# eth.net
KiCad netlist of a schematic drawn in Altium Designer
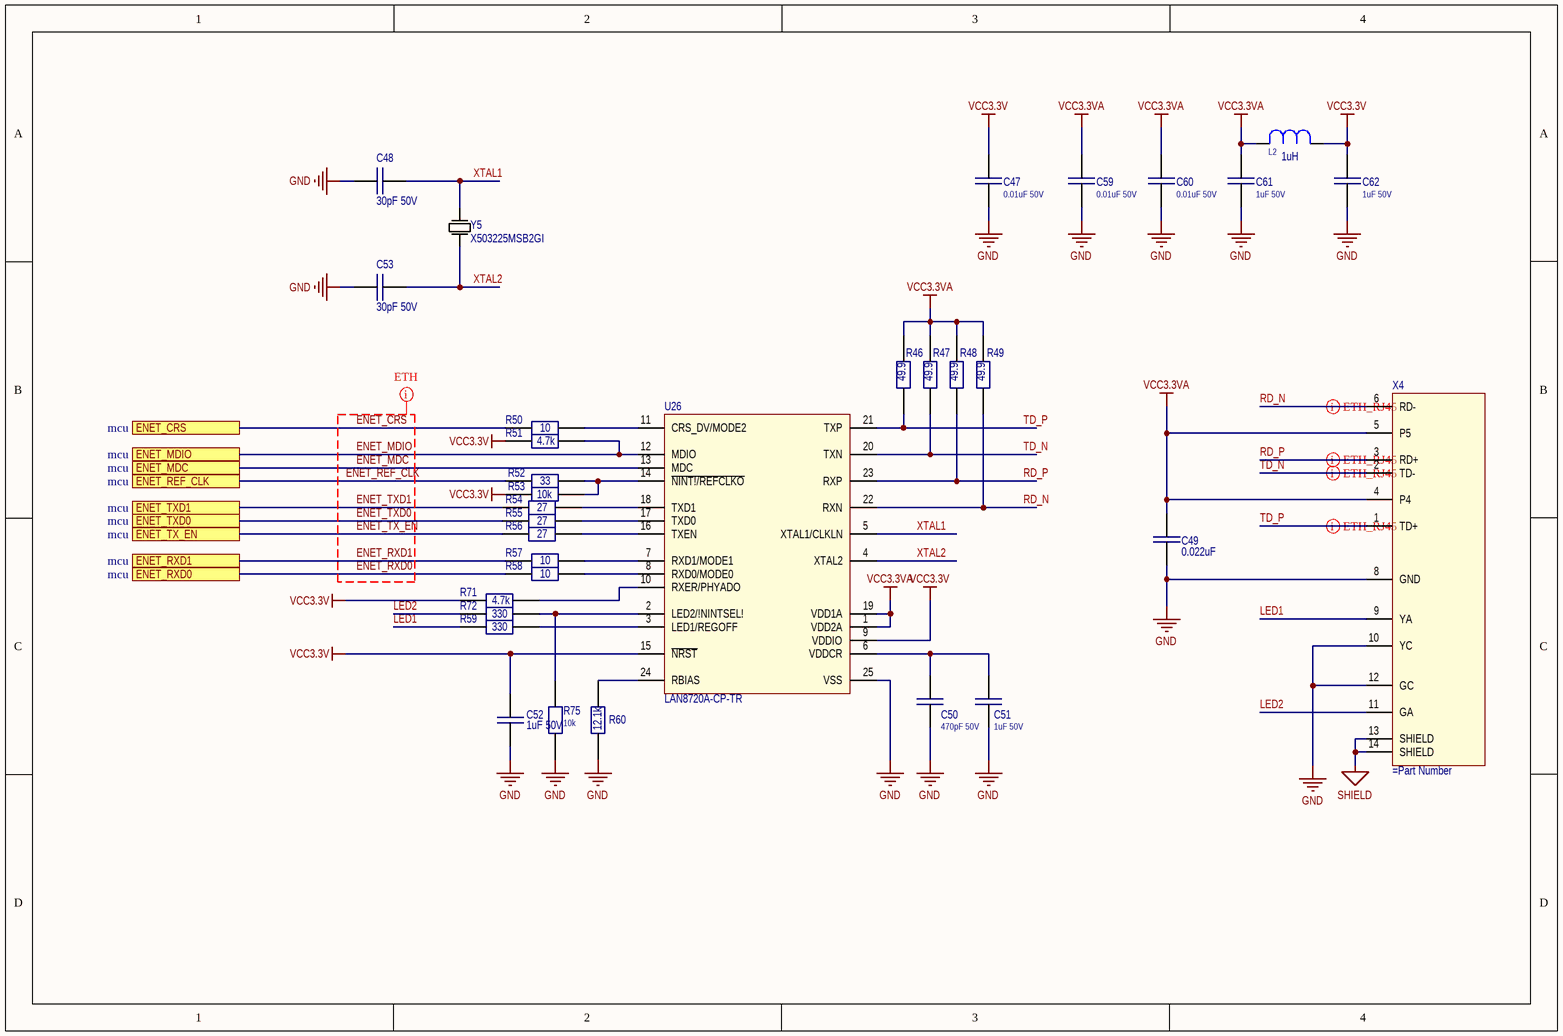
[diagram p0: eth.SchDoc]

(export (version "E")
  (design (tool "Eeschema 10.0.6"))
  (components
    (comp (ref "C47")
      (value "0.01uF 50V")
      (footprint "C_0402")
      (description "Capacitor")
      (fields (field (name "PART") "CC0402KRX7R9BB103"))
      (libsource (lib "capacitors") (part "C0402"))
    )
    (comp (ref "C48")
      (value "30pF 50V")
      (footprint "C_0603")
      (description "Capacitor")
      (fields (field (name "PART") "CC0603JRNPO9BN300"))
      (libsource (lib "capacitors") (part "CAP_SMD"))
    )
    (comp (ref "C49")
      (value "0.022uF")
      (footprint "C_0603")
      (description "Capacitor")
      (fields (field (name "PART") "CC0603KRX7R9BB223"))
      (libsource (lib "capacitors") (part "CAP_SMD"))
    )
    (comp (ref "C50")
      (value "470pF 50V")
      (footprint "C_0402")
      (description "Capacitor")
      (fields (field (name "PART") "CC0402KRX7R9BB471"))
      (libsource (lib "capacitors") (part "C0402"))
    )
    (comp (ref "C51")
      (value "1uF 50V")
      (footprint "C_0603")
      (description "Capacitor")
      (fields (field (name "PART") "CC0603KRX7R9BB105"))
      (libsource (lib "capacitors") (part "CAP_SMD"))
    )
    (comp (ref "C52")
      (value "1uF 50V")
      (footprint "C_0603")
      (description "Capacitor")
      (fields (field (name "PART") "CC0603KRX7R9BB105"))
      (libsource (lib "capacitors") (part "CAP_SMD"))
    )
    (comp (ref "C53")
      (value "30pF 50V")
      (footprint "C_0603")
      (description "Capacitor")
      (fields (field (name "PART") "CC0603JRNPO9BN300"))
      (libsource (lib "capacitors") (part "CAP_SMD"))
    )
    (comp (ref "C59")
      (value "0.01uF 50V")
      (footprint "C_0402")
      (description "Capacitor")
      (fields (field (name "PART") "CC0402KRX7R9BB103"))
      (libsource (lib "capacitors") (part "C0402"))
    )
    (comp (ref "C60")
      (value "0.01uF 50V")
      (footprint "C_0402")
      (description "Capacitor")
      (fields (field (name "PART") "CC0402KRX7R9BB103"))
      (libsource (lib "capacitors") (part "C0402"))
    )
    (comp (ref "C61")
      (value "1uF 50V")
      (footprint "C_0603")
      (description "Capacitor")
      (fields (field (name "PART") "CC0603KRX7R9BB105"))
      (libsource (lib "capacitors") (part "C0603"))
    )
    (comp (ref "C62")
      (value "1uF 50V")
      (footprint "C_0603")
      (description "Capacitor")
      (fields (field (name "PART") "CC0603KRX7R9BB105"))
      (libsource (lib "capacitors") (part "C0603"))
    )
    (comp (ref "L2")
      (value "1uH")
      (footprint "L_0603")
      (description "Inductor")
      (fields (field (name "PART") "LQM18FN1R0M00D"))
      (libsource (lib "inductors_transformers") (part "L_0603"))
    )
    (comp (ref "R46")
      (value "49.9")
      (footprint "R_0603")
      (description "Resistor")
      (fields (field (name "PART") "RC0603FR-0749R9L"))
      (libsource (lib "resistors") (part "RES_SMD"))
    )
    (comp (ref "R47")
      (value "49.9")
      (footprint "R_0603")
      (description "Resistor")
      (fields (field (name "PART") "RC0603FR-0749R9L"))
      (libsource (lib "resistors") (part "RES_SMD"))
    )
    (comp (ref "R48")
      (value "49.9")
      (footprint "R_0603")
      (description "Resistor")
      (fields (field (name "PART") "RC0603FR-0749R9L"))
      (libsource (lib "resistors") (part "RES_SMD"))
    )
    (comp (ref "R49")
      (value "49.9")
      (footprint "R_0603")
      (description "Resistor")
      (fields (field (name "PART") "RC0603FR-0749R9L"))
      (libsource (lib "resistors") (part "RES_SMD"))
    )
    (comp (ref "R50")
      (value "10")
      (footprint "R_0603")
      (description "Resistor")
      (fields (field (name "PART") "RC0603FR-0710RL"))
      (libsource (lib "resistors") (part "RES_SMD"))
    )
    (comp (ref "R51")
      (value "4.7k")
      (footprint "R_0603")
      (description "Resistor")
      (fields (field (name "PART") "RC0603FR-074K7L"))
      (libsource (lib "resistors") (part "RES_SMD"))
    )
    (comp (ref "R52")
      (value "33")
      (footprint "R_0603")
      (description "Resistor")
      (fields (field (name "PART") "RC0603FR-0733RL"))
      (libsource (lib "resistors") (part "RES_SMD"))
    )
    (comp (ref "R53")
      (value "10k")
      (footprint "R_0603")
      (description "Resistor")
      (fields (field (name "PART") "RC0603FR-0710KL"))
      (libsource (lib "resistors") (part "RES_SMD"))
    )
    (comp (ref "R54")
      (value "27")
      (footprint "R_0603")
      (description "Resistor")
      (fields (field (name "PART") "RC0402JR-0727RL"))
      (libsource (lib "resistors") (part "RES_SMD"))
    )
    (comp (ref "R55")
      (value "27")
      (footprint "R_0603")
      (description "Resistor")
      (fields (field (name "PART") "RC0402JR-0727RL"))
      (libsource (lib "resistors") (part "RES_SMD"))
    )
    (comp (ref "R56")
      (value "27")
      (footprint "R_0603")
      (description "Resistor")
      (fields (field (name "PART") "RC0402JR-0727RL"))
      (libsource (lib "resistors") (part "RES_SMD"))
    )
    (comp (ref "R57")
      (value "10")
      (footprint "R_0603")
      (description "Resistor")
      (fields (field (name "PART") "RC0603FR-0710RL"))
      (libsource (lib "resistors") (part "RES_SMD"))
    )
    (comp (ref "R58")
      (value "10")
      (footprint "R_0603")
      (description "Resistor")
      (fields (field (name "PART") "RC0603FR-0710RL"))
      (libsource (lib "resistors") (part "RES_SMD"))
    )
    (comp (ref "R59")
      (value "330")
      (footprint "R_0603")
      (description "Resistor")
      (fields (field (name "PART") "RC0603FR-07330RL"))
      (libsource (lib "resistors") (part "RES_SMD"))
    )
    (comp (ref "R60")
      (value "12.1k")
      (footprint "R_0603")
      (description "Resistor")
      (fields (field (name "PART") "RC0603FR-0712K1L"))
      (libsource (lib "resistors") (part "RES_SMD"))
    )
    (comp (ref "R71")
      (value "4.7k")
      (footprint "R_0603")
      (description "Resistor")
      (fields (field (name "PART") "RC0603FR-074K7L"))
      (libsource (lib "resistors") (part "RES_SMD"))
    )
    (comp (ref "R72")
      (value "330")
      (footprint "R_0603")
      (description "Resistor")
      (fields (field (name "PART") "RC0603FR-07330RL"))
      (libsource (lib "resistors") (part "RES_SMD"))
    )
    (comp (ref "R75")
      (value "10k")
      (footprint "R_0603")
      (description "Resistor")
      (fields (field (name "PART") "RC0603FR-0710KL"))
      (libsource (lib "bmplc") (part "RES_SMD"))
    )
    (comp (ref "U26")
      (value "LAN8720A-CP-TR")
      (footprint "QFN50P400X400X100-25N")
      (description "Phy Eth 2/2 Transceiver Full RMII 24-QFN-EP _4x4_")
      (fields (field (name "MF") "Microchip") (field (name "MP") "LAN8720A-CP"))
      (libsource (lib "discret_ic") (part "LAN8720"))
    )
    (comp (ref "X4")
      (value "~")
      (footprint "RJ45-TH_HR915340A")
      (description "DIP RJ45 Connector;")
      (fields (field (name "MP") "HR915340A"))
      (libsource (lib "connectors_socets") (part "HR915340A"))
    )
    (comp (ref "Y5")
      (value "X503225MSB2GI")
      (footprint "X5032")
      (description "Crystal Oscillator")
      (libsource (lib "crystals_oscillators") (part "X503212MSB2GI"))
    )
  )
  (nets
    (net (code "1") (name "/ENET_CRS") (class "Default")
      (node (ref "R50") (pin "1") (pinfunction "1_1") (pintype "passive"))
    )
    (net (code "2") (name "/ENET_MDC") (class "Default")
      (node (ref "U26") (pin "13") (pinfunction "MDC_13") (pintype "passive"))
    )
    (net (code "3") (name "/ENET_MDIO") (class "Default")
      (node (ref "R51") (pin "2") (pinfunction "2_2") (pintype "passive"))
      (node (ref "U26") (pin "12") (pinfunction "MDIO_12") (pintype "passive"))
    )
    (net (code "4") (name "/ENET_REF_CLK") (class "Default")
      (node (ref "R52") (pin "1") (pinfunction "1_1") (pintype "passive"))
    )
    (net (code "5") (name "/ENET_RXD0") (class "Default")
      (node (ref "R58") (pin "1") (pinfunction "1_1") (pintype "passive"))
    )
    (net (code "6") (name "/ENET_RXD1") (class "Default")
      (node (ref "R57") (pin "1") (pinfunction "1_1") (pintype "passive"))
    )
    (net (code "7") (name "/ENET_TXD0") (class "Default")
      (node (ref "R55") (pin "1") (pinfunction "1_1") (pintype "passive"))
    )
    (net (code "8") (name "/ENET_TXD1") (class "Default")
      (node (ref "R54") (pin "1") (pinfunction "1_1") (pintype "passive"))
    )
    (net (code "9") (name "/ENET_TX_EN") (class "Default")
      (node (ref "R56") (pin "1") (pinfunction "1_1") (pintype "passive"))
    )
    (net (code "10") (name "/LED1") (class "Default")
      (node (ref "R59") (pin "2") (pinfunction "2_2") (pintype "passive"))
      (node (ref "X4") (pin "9") (pinfunction "YA_9") (pintype "passive"))
    )
    (net (code "11") (name "/LED2") (class "Default")
      (node (ref "R72") (pin "2") (pinfunction "2_2") (pintype "passive"))
      (node (ref "X4") (pin "11") (pinfunction "GA_11") (pintype "passive"))
    )
    (net (code "12") (name "/RD_N") (class "Default")
      (node (ref "R49") (pin "1") (pinfunction "1_1") (pintype "passive"))
      (node (ref "U26") (pin "22") (pinfunction "RXN_22") (pintype "passive"))
      (node (ref "X4") (pin "6") (pinfunction "RD-_6") (pintype "passive"))
    )
    (net (code "13") (name "/RD_P") (class "Default")
      (node (ref "R48") (pin "1") (pinfunction "1_1") (pintype "passive"))
      (node (ref "U26") (pin "23") (pinfunction "RXP_23") (pintype "passive"))
      (node (ref "X4") (pin "3") (pinfunction "RD+_3") (pintype "passive"))
    )
    (net (code "14") (name "/TD_N") (class "Default")
      (node (ref "R47") (pin "1") (pinfunction "1_1") (pintype "passive"))
      (node (ref "U26") (pin "20") (pinfunction "TXN_20") (pintype "passive"))
      (node (ref "X4") (pin "2") (pinfunction "TD-_2") (pintype "passive"))
    )
    (net (code "15") (name "/TD_P") (class "Default")
      (node (ref "R46") (pin "1") (pinfunction "1_1") (pintype "passive"))
      (node (ref "U26") (pin "21") (pinfunction "TXP_21") (pintype "passive"))
      (node (ref "X4") (pin "1") (pinfunction "TD+_1") (pintype "passive"))
    )
    (net (code "16") (name "/XTAL1") (class "Default")
      (node (ref "C48") (pin "1") (pinfunction "1_1") (pintype "passive"))
      (node (ref "U26") (pin "5") (pinfunction "XTAL1/CLKLN_5") (pintype "passive"))
      (node (ref "Y5") (pin "1") (pinfunction "1_1") (pintype "passive"))
    )
    (net (code "17") (name "/XTAL2") (class "Default")
      (node (ref "C53") (pin "1") (pinfunction "1_1") (pintype "passive"))
      (node (ref "U26") (pin "4") (pinfunction "XTAL2_4") (pintype "passive"))
      (node (ref "Y5") (pin "2") (pinfunction "2_2") (pintype "passive"))
    )
    (net (code "18") (name "GND") (class "Default")
      (node (ref "C47") (pin "2") (pinfunction "2_2") (pintype "passive"))
      (node (ref "C48") (pin "2") (pinfunction "2_2") (pintype "passive"))
      (node (ref "C49") (pin "1") (pinfunction "1_1") (pintype "passive"))
      (node (ref "C50") (pin "2") (pinfunction "2_2") (pintype "passive"))
      (node (ref "C51") (pin "1") (pinfunction "1_1") (pintype "passive"))
      (node (ref "C52") (pin "1") (pinfunction "1_1") (pintype "passive"))
      (node (ref "C53") (pin "2") (pinfunction "2_2") (pintype "passive"))
      (node (ref "C59") (pin "2") (pinfunction "2_2") (pintype "passive"))
      (node (ref "C60") (pin "2") (pinfunction "2_2") (pintype "passive"))
      (node (ref "C61") (pin "1") (pinfunction "1_1") (pintype "passive"))
      (node (ref "C62") (pin "1") (pinfunction "1_1") (pintype "passive"))
      (node (ref "R60") (pin "1") (pinfunction "1_1") (pintype "passive"))
      (node (ref "R75") (pin "1") (pinfunction "1_1") (pintype "passive"))
      (node (ref "U26") (pin "25") (pinfunction "VSS_25") (pintype "passive"))
      (node (ref "X4") (pin "10") (pinfunction "YC_10") (pintype "passive"))
      (node (ref "X4") (pin "12") (pinfunction "GC_12") (pintype "passive"))
      (node (ref "X4") (pin "8") (pinfunction "GND_8") (pintype "power_in"))
    )
    (net (code "19") (name "Net-(U26-CRS_DV{slash}MODE2)") (class "Default")
      (node (ref "R50") (pin "2") (pinfunction "2_2") (pintype "passive"))
      (node (ref "U26") (pin "11") (pinfunction "CRS_DV/MODE2_11") (pintype "passive"))
    )
    (net (code "20") (name "Net-(U26-LED1{slash}REGOFF)") (class "Default")
      (node (ref "R59") (pin "1") (pinfunction "1_1") (pintype "passive"))
      (node (ref "U26") (pin "3") (pinfunction "LED1/REGOFF_3") (pintype "passive"))
    )
    (net (code "21") (name "Net-(U26-LED2{slash}!NINTSEL!)") (class "Default")
      (node (ref "R72") (pin "1") (pinfunction "1_1") (pintype "passive"))
      (node (ref "R75") (pin "2") (pinfunction "2_2") (pintype "passive"))
      (node (ref "U26") (pin "2") (pinfunction "LED2/!NINTSEL!_2") (pintype "passive"))
    )
    (net (code "22") (name "Net-(U26-RBIAS)") (class "Default")
      (node (ref "R60") (pin "2") (pinfunction "2_2") (pintype "passive"))
      (node (ref "U26") (pin "24") (pinfunction "RBIAS_24") (pintype "passive"))
    )
    (net (code "23") (name "Net-(U26-RXD0{slash}MODE0)") (class "Default")
      (node (ref "R58") (pin "2") (pinfunction "2_2") (pintype "passive"))
      (node (ref "U26") (pin "8") (pinfunction "RXD0/MODE0_8") (pintype "passive"))
    )
    (net (code "24") (name "Net-(U26-RXD1{slash}MODE1)") (class "Default")
      (node (ref "R57") (pin "2") (pinfunction "2_2") (pintype "passive"))
      (node (ref "U26") (pin "7") (pinfunction "RXD1/MODE1_7") (pintype "passive"))
    )
    (net (code "25") (name "Net-(U26-RXER{slash}PHYADO)") (class "Default")
      (node (ref "R71") (pin "2") (pinfunction "2_2") (pintype "passive"))
      (node (ref "U26") (pin "10") (pinfunction "RXER/PHYADO_10") (pintype "passive"))
    )
    (net (code "26") (name "Net-(U26-TXD0)") (class "Default")
      (node (ref "R55") (pin "2") (pinfunction "2_2") (pintype "passive"))
      (node (ref "U26") (pin "17") (pinfunction "TXD0_17") (pintype "passive"))
    )
    (net (code "27") (name "Net-(U26-TXD1)") (class "Default")
      (node (ref "R54") (pin "2") (pinfunction "2_2") (pintype "passive"))
      (node (ref "U26") (pin "18") (pinfunction "TXD1_18") (pintype "passive"))
    )
    (net (code "28") (name "Net-(U26-TXEN)") (class "Default")
      (node (ref "R56") (pin "2") (pinfunction "2_2") (pintype "passive"))
      (node (ref "U26") (pin "16") (pinfunction "TXEN_16") (pintype "passive"))
    )
    (net (code "29") (name "Net-(U26-VDDCR)") (class "Default")
      (node (ref "C50") (pin "1") (pinfunction "1_1") (pintype "passive"))
      (node (ref "C51") (pin "2") (pinfunction "2_2") (pintype "passive"))
      (node (ref "U26") (pin "6") (pinfunction "VDDCR_6") (pintype "passive"))
    )
    (net (code "30") (name "Net-(U26-~{NINT!{slash}REFCLKO})") (class "Default")
      (node (ref "R52") (pin "2") (pinfunction "2_2") (pintype "passive"))
      (node (ref "R53") (pin "1") (pinfunction "1_1") (pintype "passive"))
      (node (ref "U26") (pin "14") (pinfunction "~{NINT!/REFCLKO}_14") (pintype "passive"))
    )
    (net (code "31") (name "SHIELD") (class "Default")
      (node (ref "X4") (pin "13") (pinfunction "SHIELD_13") (pintype "passive"))
      (node (ref "X4") (pin "14") (pinfunction "SHIELD_14") (pintype "passive"))
    )
    (net (code "32") (name "VCC3.3V") (class "Default")
      (node (ref "C47") (pin "1") (pinfunction "1_1") (pintype "passive"))
      (node (ref "C52") (pin "2") (pinfunction "2_2") (pintype "passive"))
      (node (ref "C62") (pin "2") (pinfunction "2_2") (pintype "passive"))
      (node (ref "L2") (pin "2") (pintype "passive"))
      (node (ref "R51") (pin "1") (pinfunction "1_1") (pintype "passive"))
      (node (ref "R53") (pin "2") (pinfunction "2_2") (pintype "passive"))
      (node (ref "R71") (pin "1") (pinfunction "1_1") (pintype "passive"))
      (node (ref "U26") (pin "15") (pinfunction "~{NRST}_15") (pintype "passive"))
      (node (ref "U26") (pin "9") (pinfunction "VDDIO_9") (pintype "passive"))
    )
    (net (code "33") (name "VCC3.3VA") (class "Default")
      (node (ref "C49") (pin "2") (pinfunction "2_2") (pintype "passive"))
      (node (ref "C59") (pin "1") (pinfunction "1_1") (pintype "passive"))
      (node (ref "C60") (pin "1") (pinfunction "1_1") (pintype "passive"))
      (node (ref "C61") (pin "2") (pinfunction "2_2") (pintype "passive"))
      (node (ref "L2") (pin "1") (pintype "passive"))
      (node (ref "R46") (pin "2") (pinfunction "2_2") (pintype "passive"))
      (node (ref "R47") (pin "2") (pinfunction "2_2") (pintype "passive"))
      (node (ref "R48") (pin "2") (pinfunction "2_2") (pintype "passive"))
      (node (ref "R49") (pin "2") (pinfunction "2_2") (pintype "passive"))
      (node (ref "U26") (pin "1") (pinfunction "VDD2A_1") (pintype "passive"))
      (node (ref "U26") (pin "19") (pinfunction "VDD1A_19") (pintype "passive"))
      (node (ref "X4") (pin "4") (pinfunction "P4_4") (pintype "passive"))
      (node (ref "X4") (pin "5") (pinfunction "P5_5") (pintype "passive"))
    )
  )
)
